# WP_STM32.net
KiCad netlist of a schematic drawn in Altium Designer
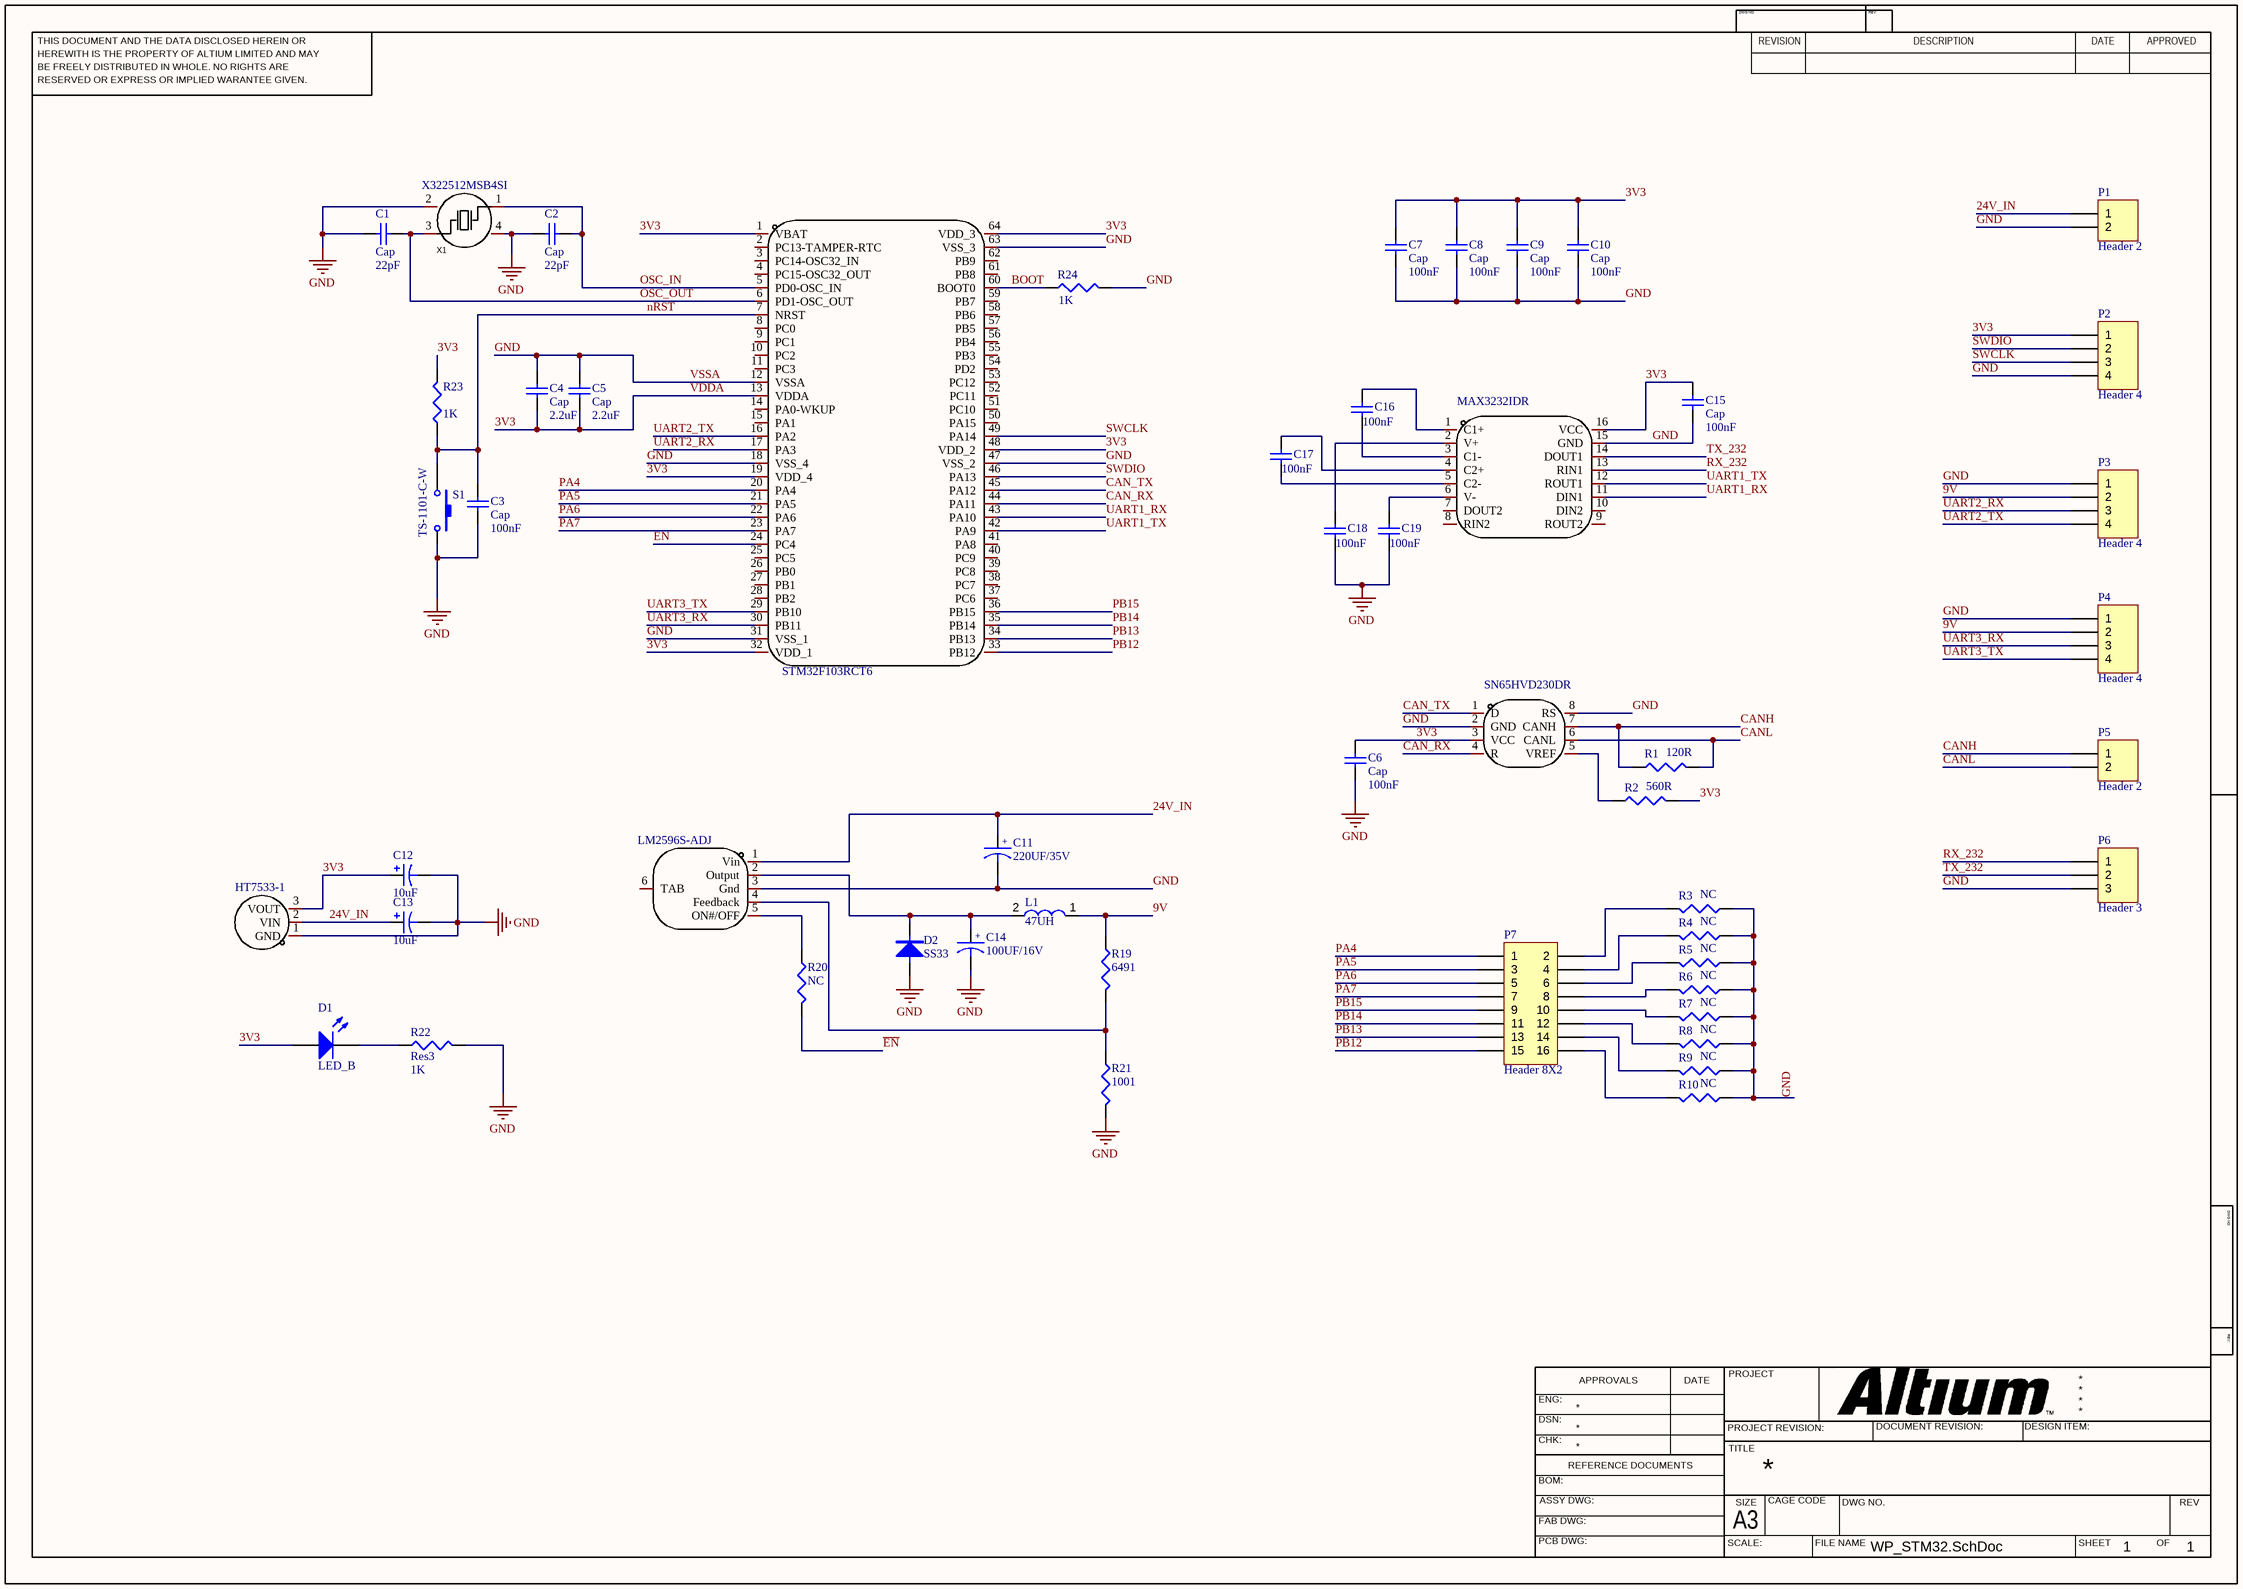
[diagram p0: WP_STM32.SchDoc]

(export (version "E")
  (design (tool "Eeschema 10.0.6"))
  (components
    (comp (ref "C1")
      (value "Cap")
      (footprint "0603C")
      (description "Capacitor")
      (fields (field (name "ALTIUM_VALUE") "22pF") (field (name "PUBLISHER") "Altium Limited"))
      (libsource (lib "Miscellaneous Devices") (part "Cap"))
    )
    (comp (ref "C2")
      (value "Cap")
      (footprint "0603C")
      (description "Capacitor")
      (fields (field (name "ALTIUM_VALUE") "22pF") (field (name "PUBLISHER") "Altium Limited"))
      (libsource (lib "Miscellaneous Devices") (part "Cap"))
    )
    (comp (ref "C3")
      (value "Cap")
      (footprint "0603C")
      (description "Capacitor")
      (fields (field (name "ALTIUM_VALUE") "100nF") (field (name "PUBLISHER") "Altium Limited"))
      (libsource (lib "Miscellaneous Devices") (part "Cap"))
    )
    (comp (ref "C4")
      (value "Cap")
      (footprint "0603C")
      (description "Capacitor")
      (fields (field (name "ALTIUM_VALUE") "2.2uF") (field (name "PUBLISHER") "Altium Limited"))
      (libsource (lib "Miscellaneous Devices") (part "Cap"))
    )
    (comp (ref "C5")
      (value "Cap")
      (footprint "0603C")
      (description "Capacitor")
      (fields (field (name "ALTIUM_VALUE") "2.2uF") (field (name "PUBLISHER") "Altium Limited"))
      (libsource (lib "Miscellaneous Devices") (part "Cap"))
    )
    (comp (ref "C6")
      (value "Cap")
      (footprint "0603C")
      (description "Capacitor")
      (fields (field (name "ALTIUM_VALUE") "100nF") (field (name "PUBLISHER") "Altium Limited"))
      (libsource (lib "Miscellaneous Devices") (part "Cap"))
    )
    (comp (ref "C7")
      (value "Cap")
      (footprint "0603C")
      (description "Capacitor")
      (fields (field (name "ALTIUM_VALUE") "100nF") (field (name "PUBLISHER") "Altium Limited"))
      (libsource (lib "Miscellaneous Devices") (part "Cap"))
    )
    (comp (ref "C8")
      (value "Cap")
      (footprint "0603C")
      (description "Capacitor")
      (fields (field (name "ALTIUM_VALUE") "100nF") (field (name "PUBLISHER") "Altium Limited"))
      (libsource (lib "Miscellaneous Devices") (part "Cap"))
    )
    (comp (ref "C9")
      (value "Cap")
      (footprint "0603C")
      (description "Capacitor")
      (fields (field (name "ALTIUM_VALUE") "100nF") (field (name "PUBLISHER") "Altium Limited"))
      (libsource (lib "Miscellaneous Devices") (part "Cap"))
    )
    (comp (ref "C10")
      (value "Cap")
      (footprint "0603C")
      (description "Capacitor")
      (fields (field (name "ALTIUM_VALUE") "100nF") (field (name "PUBLISHER") "Altium Limited"))
      (libsource (lib "Miscellaneous Devices") (part "Cap"))
    )
    (comp (ref "C11")
      (value "220UF/35V")
      (footprint "CAP-TH_BD8.0-P3.50-D0.6-FD")
      (libsource (lib "*") (part "C+"))
    )
    (comp (ref "C12")
      (value "10uF")
      (footprint "LC-CASE-A_3216")
      (description "Polarized Capacitor (Surface Mount)")
      (fields (field (name "Comment") "Cap Pol3") (field (name "PUBLISHER") "Altium Limited"))
      (libsource (lib "Miscellaneous Devices") (part "Cap Pol3"))
    )
    (comp (ref "C13")
      (value "10uF")
      (footprint "LC-CASE-A_3216")
      (description "Polarized Capacitor (Surface Mount)")
      (fields (field (name "Comment") "Cap Pol3") (field (name "PUBLISHER") "Altium Limited"))
      (libsource (lib "Miscellaneous Devices") (part "Cap Pol3"))
    )
    (comp (ref "C14")
      (value "100UF/16V")
      (footprint "CAP-TH_BD5.0-P2.00-D0.5-FD-1")
      (libsource (lib "*") (part "C+"))
    )
    (comp (ref "C15")
      (value "Cap")
      (footprint "0603C")
      (description "Capacitor")
      (fields (field (name "ALTIUM_VALUE") "100nF") (field (name "PUBLISHER") "Altium Limited"))
      (libsource (lib "Miscellaneous Devices") (part "Cap"))
    )
    (comp (ref "C16")
      (value "100nF")
      (footprint "0603C")
      (description "Capacitor")
      (fields (field (name "Comment") "Cap") (field (name "PUBLISHER") "Altium Limited"))
      (libsource (lib "Miscellaneous Devices") (part "Cap"))
    )
    (comp (ref "C17")
      (value "100nF")
      (footprint "0603C")
      (description "Capacitor")
      (fields (field (name "Comment") "Cap") (field (name "PUBLISHER") "Altium Limited"))
      (libsource (lib "Miscellaneous Devices") (part "Cap"))
    )
    (comp (ref "C18")
      (value "100nF")
      (footprint "0603C")
      (description "Capacitor")
      (fields (field (name "Comment") "Cap") (field (name "PUBLISHER") "Altium Limited"))
      (libsource (lib "Miscellaneous Devices") (part "Cap"))
    )
    (comp (ref "C19")
      (value "100nF")
      (footprint "0603C")
      (description "Capacitor")
      (fields (field (name "Comment") "Cap") (field (name "PUBLISHER") "Altium Limited"))
      (libsource (lib "Miscellaneous Devices") (part "Cap"))
    )
    (comp (ref "D1")
      (value "LED_B")
      (footprint "0603D")
      (description "Typical RED, GREEN, YELLOW, AMBER GaAs LED")
      (fields (field (name "PUBLISHER") "Altium Limited"))
      (libsource (lib "Miscellaneous Devices") (part "LED2"))
    )
    (comp (ref "D2") (value "SS33") (footprint "LC-SMA(DO-214AC)") (libsource (lib "*") (part "D")))
    (comp (ref "L1")
      (value "47UH")
      (footprint "IND-SMD_L10.8-W10.0_SLO1040H")
      (libsource (lib "*") (part "L"))
    )
    (comp (ref "P1")
      (value "Header 2")
      (footprint "KF350-2P")
      (description "Header, 2-Pin")
      (fields (field (name "PUBLISHER") "Altium Limited"))
      (libsource (lib "Miscellaneous Connectors") (part "Header 2"))
    )
    (comp (ref "P2")
      (value "Header 4")
      (footprint "MX 1.25-LI-4P")
      (description "Header, 4-Pin")
      (fields (field (name "PUBLISHER") "Altium Limited"))
      (libsource (lib "Miscellaneous Connectors") (part "Header 4"))
    )
    (comp (ref "P3")
      (value "Header 4")
      (footprint "MX 1.25-LI-4P")
      (description "Header, 4-Pin")
      (fields (field (name "PUBLISHER") "Altium Limited"))
      (libsource (lib "Miscellaneous Connectors") (part "Header 4"))
    )
    (comp (ref "P4")
      (value "Header 4")
      (footprint "MX 1.25-LI-4P")
      (description "Header, 4-Pin")
      (fields (field (name "PUBLISHER") "Altium Limited"))
      (libsource (lib "Miscellaneous Connectors") (part "Header 4"))
    )
    (comp (ref "P5")
      (value "Header 2")
      (footprint "MX 1.25-LI-2P")
      (description "Header, 2-Pin")
      (fields (field (name "PUBLISHER") "Altium Limited"))
      (libsource (lib "Miscellaneous Connectors") (part "Header 2"))
    )
    (comp (ref "P6")
      (value "Header 3")
      (footprint "MX 1.25-LI-3P")
      (description "Header, 3-Pin")
      (fields (field (name "PUBLISHER") "Altium Limited"))
      (libsource (lib "Miscellaneous Connectors") (part "Header 3"))
    )
    (comp (ref "P7")
      (value "Header 8X2")
      (footprint "HDR2X8")
      (description "Header, 8-Pin, Dual row")
      (fields (field (name "PUBLISHER") "Altium Limited"))
      (libsource (lib "Miscellaneous Connectors") (part "Header 8X2"))
    )
    (comp (ref "R1")
      (value "120R")
      (footprint "0603R")
      (description "Resistor")
      (fields (field (name "Comment") "Res3") (field (name "PUBLISHER") "Altium Limited"))
      (libsource (lib "Miscellaneous Devices") (part "Res3"))
    )
    (comp (ref "R2")
      (value "560R")
      (footprint "0603R")
      (description "Resistor")
      (fields (field (name "Comment") "Res3") (field (name "PUBLISHER") "Altium Limited"))
      (libsource (lib "Miscellaneous Devices") (part "Res3"))
    )
    (comp (ref "R3")
      (value "NC")
      (footprint "0603R")
      (description "Resistor")
      (fields (field (name "Comment") "Res3") (field (name "PUBLISHER") "Altium Limited"))
      (libsource (lib "Miscellaneous Devices") (part "Res3"))
    )
    (comp (ref "R4")
      (value "NC")
      (footprint "0603R")
      (description "Resistor")
      (fields (field (name "Comment") "Res3") (field (name "PUBLISHER") "Altium Limited"))
      (libsource (lib "Miscellaneous Devices") (part "Res3"))
    )
    (comp (ref "R5")
      (value "NC")
      (footprint "0603R")
      (description "Resistor")
      (fields (field (name "Comment") "Res3") (field (name "PUBLISHER") "Altium Limited"))
      (libsource (lib "Miscellaneous Devices") (part "Res3"))
    )
    (comp (ref "R6")
      (value "NC")
      (footprint "0603R")
      (description "Resistor")
      (fields (field (name "Comment") "Res3") (field (name "PUBLISHER") "Altium Limited"))
      (libsource (lib "Miscellaneous Devices") (part "Res3"))
    )
    (comp (ref "R7")
      (value "NC")
      (footprint "0603R")
      (description "Resistor")
      (fields (field (name "Comment") "Res3") (field (name "PUBLISHER") "Altium Limited"))
      (libsource (lib "Miscellaneous Devices") (part "Res3"))
    )
    (comp (ref "R8")
      (value "NC")
      (footprint "0603R")
      (description "Resistor")
      (fields (field (name "Comment") "Res3") (field (name "PUBLISHER") "Altium Limited"))
      (libsource (lib "Miscellaneous Devices") (part "Res3"))
    )
    (comp (ref "R9")
      (value "NC")
      (footprint "0603R")
      (description "Resistor")
      (fields (field (name "Comment") "Res3") (field (name "PUBLISHER") "Altium Limited"))
      (libsource (lib "Miscellaneous Devices") (part "Res3"))
    )
    (comp (ref "R10")
      (value "NC")
      (footprint "0603R")
      (description "Resistor")
      (fields (field (name "Comment") "Res3") (field (name "PUBLISHER") "Altium Limited"))
      (libsource (lib "Miscellaneous Devices") (part "Res3"))
    )
    (comp (ref "R19")
      (value "6491")
      (footprint "0603R")
      (description "Resistor")
      (fields (field (name "Comment") "Res3") (field (name "PUBLISHER") "Altium Limited"))
      (libsource (lib "Miscellaneous Devices") (part "Res3"))
    )
    (comp (ref "R20")
      (value "NC")
      (footprint "0603R")
      (description "Resistor")
      (fields (field (name "Comment") "Res3") (field (name "PUBLISHER") "Altium Limited"))
      (libsource (lib "Miscellaneous Devices") (part "Res3"))
    )
    (comp (ref "R21")
      (value "1001")
      (footprint "0603R")
      (description "Resistor")
      (fields (field (name "Comment") "Res3") (field (name "PUBLISHER") "Altium Limited"))
      (libsource (lib "Miscellaneous Devices") (part "Res3"))
    )
    (comp (ref "R22")
      (value "Res3")
      (footprint "0603R")
      (description "Resistor")
      (fields (field (name "ALTIUM_VALUE") "1K") (field (name "PUBLISHER") "Altium Limited"))
      (libsource (lib "Miscellaneous Devices") (part "Res3"))
    )
    (comp (ref "R23")
      (value "1K")
      (footprint "0603R")
      (description "Resistor")
      (fields (field (name "Comment") "Res3") (field (name "PUBLISHER") "Altium Limited"))
      (libsource (lib "Miscellaneous Devices") (part "Res3"))
    )
    (comp (ref "R24")
      (value "1K")
      (footprint "0603R")
      (description "Resistor")
      (fields (field (name "Comment") "Res3") (field (name "PUBLISHER") "Altium Limited"))
      (libsource (lib "Miscellaneous Devices") (part "Res3"))
    )
    (comp (ref "S1")
      (value "TS-1101-C-W")
      (footprint "SW-SMD_L3.9-W3.0-P4.45")
      (description "Switch")
      (fields (field (name "PUBLISHER") "Altium Limited"))
      (libsource (lib "Miscellaneous Devices") (part "SW-PB"))
    )
    (comp (ref "U1")
      (value "STM32F103RCT6")
      (footprint "LQFP-64_L10.0-W10.0-P0.50-LS12.0-BL")
      (fields (field (name "MANUFACTURER") "ST(意法半导体)"))
      (libsource (lib "altium-import") (part "root_0_STM32F103RCT6_"))
    )
    (comp (ref "U2")
      (value "SN65HVD230DR")
      (footprint "SOP8")
      (fields (field (name "MANUFACTURER") "TI(德州仪器)"))
      (libsource (lib "altium-import") (part "root_0_SN65HVD230DR_"))
    )
    (comp (ref "U3")
      (value "LM2596S-ADJ")
      (footprint "TO-263-5_L10.2-W8.9-P1.70-BR")
      (fields (field (name "MANUFACTURER") "UMW(友台半导体)"))
      (libsource (lib "altium-import") (part "root_0_mirrored_LM2596S-ADJ_C347423_"))
    )
    (comp (ref "U4")
      (value "HT7533-1")
      (footprint "SOT89")
      (fields (field (name "MANUFACTURER") "UMW(友台半导体)"))
      (libsource (lib "altium-import") (part "root_2_HT7533-1_C347186_"))
    )
    (comp (ref "U5")
      (value "MAX3232IDR")
      (footprint "SOP16")
      (fields (field (name "MANUFACTURER") "TI(德州仪器)"))
      (libsource (lib "altium-import") (part "root_0_MAX3232IDR_"))
    )
    (comp (ref "X1")
      (value "X322512MSB4SI")
      (footprint "OSC-SMD_4P-L3.2-W2.5-BL")
      (fields (field (name "MANUFACTURER") "YXC(扬兴晶振)"))
      (libsource (lib "altium-import") (part "root_2_X322512MSB4SI_"))
    )
  )
  (nets
    (net (code "1") (name "/3V3") (class "Default")
      (node (ref "C10") (pin "2") (pinfunction "2_2") (pintype "passive"))
      (node (ref "C12") (pin "1") (pinfunction "1_1") (pintype "passive"))
      (node (ref "C15") (pin "1") (pinfunction "1_1") (pintype "passive"))
      (node (ref "C4") (pin "1") (pinfunction "1_1") (pintype "passive"))
      (node (ref "C5") (pin "1") (pinfunction "1_1") (pintype "passive"))
      (node (ref "C6") (pin "2") (pinfunction "2_2") (pintype "passive"))
      (node (ref "C7") (pin "2") (pinfunction "2_2") (pintype "passive"))
      (node (ref "C8") (pin "2") (pinfunction "2_2") (pintype "passive"))
      (node (ref "C9") (pin "2") (pinfunction "2_2") (pintype "passive"))
      (node (ref "D1") (pin "1") (pinfunction "A_1") (pintype "passive"))
      (node (ref "P2") (pin "1") (pinfunction "1_1") (pintype "passive"))
      (node (ref "R2") (pin "2") (pinfunction "2_2") (pintype "passive"))
      (node (ref "R23") (pin "2") (pinfunction "2_2") (pintype "passive"))
      (node (ref "U1") (pin "1") (pinfunction "VBAT_1") (pintype "passive"))
      (node (ref "U1") (pin "13") (pinfunction "VDDA_13") (pintype "passive"))
      (node (ref "U1") (pin "19") (pinfunction "VDD_4_19") (pintype "passive"))
      (node (ref "U1") (pin "32") (pinfunction "VDD_1_32") (pintype "passive"))
      (node (ref "U1") (pin "48") (pinfunction "VDD_2_48") (pintype "passive"))
      (node (ref "U1") (pin "64") (pinfunction "VDD_3_64") (pintype "passive"))
      (node (ref "U2") (pin "3") (pinfunction "VCC_3") (pintype "passive"))
      (node (ref "U4") (pin "3") (pinfunction "VOUT_3") (pintype "passive"))
      (node (ref "U5") (pin "16") (pinfunction "VCC_16") (pintype "passive"))
    )
    (net (code "2") (name "/9V") (class "Default")
      (node (ref "L1") (pin "1") (pinfunction "1_1") (pintype "passive"))
      (node (ref "P3") (pin "2") (pinfunction "2_2") (pintype "passive"))
      (node (ref "P4") (pin "2") (pinfunction "2_2") (pintype "passive"))
      (node (ref "R19") (pin "1") (pinfunction "1_1") (pintype "passive"))
    )
    (net (code "3") (name "/24V_IN") (class "Default")
      (node (ref "C11") (pin "1") (pinfunction "1_1") (pintype "passive"))
      (node (ref "C13") (pin "1") (pinfunction "1_1") (pintype "passive"))
      (node (ref "P1") (pin "1") (pinfunction "1_1") (pintype "passive"))
      (node (ref "U3") (pin "1") (pinfunction "Vin_1") (pintype "passive"))
      (node (ref "U4") (pin "2") (pinfunction "VIN_2") (pintype "passive"))
    )
    (net (code "5") (name "/BOOT") (class "Default")
      (node (ref "R24") (pin "1") (pinfunction "1_1") (pintype "passive"))
      (node (ref "U1") (pin "60") (pinfunction "BOOT0_60") (pintype "passive"))
    )
    (net (code "6") (name "/CANH") (class "Default")
      (node (ref "P5") (pin "1") (pinfunction "1_1") (pintype "passive"))
      (node (ref "R1") (pin "1") (pinfunction "1_1") (pintype "passive"))
      (node (ref "U2") (pin "7") (pinfunction "CANH_7") (pintype "passive"))
    )
    (net (code "7") (name "/CANL") (class "Default")
      (node (ref "P5") (pin "2") (pinfunction "2_2") (pintype "passive"))
      (node (ref "R1") (pin "2") (pinfunction "2_2") (pintype "passive"))
      (node (ref "U2") (pin "6") (pinfunction "CANL_6") (pintype "passive"))
    )
    (net (code "8") (name "/CAN_RX") (class "Default")
      (node (ref "U1") (pin "44") (pinfunction "PA11_44") (pintype "passive"))
      (node (ref "U2") (pin "4") (pinfunction "R_4") (pintype "passive"))
    )
    (net (code "9") (name "/CAN_TX") (class "Default")
      (node (ref "U1") (pin "45") (pinfunction "PA12_45") (pintype "passive"))
      (node (ref "U2") (pin "1") (pinfunction "D_1") (pintype "passive"))
    )
    (net (code "10") (name "/OSC_IN") (class "Default")
      (node (ref "C2") (pin "2") (pinfunction "2_2") (pintype "passive"))
      (node (ref "U1") (pin "5") (pinfunction "PD0-OSC_IN_5") (pintype "passive"))
      (node (ref "X1") (pin "1") (pinfunction "OSC1_1") (pintype "passive"))
    )
    (net (code "11") (name "/OSC_OUT") (class "Default")
      (node (ref "C1") (pin "2") (pinfunction "2_2") (pintype "passive"))
      (node (ref "U1") (pin "6") (pinfunction "PD1-OSC_OUT_6") (pintype "passive"))
      (node (ref "X1") (pin "3") (pinfunction "OSC2_3") (pintype "passive"))
    )
    (net (code "12") (name "/PA4") (class "Default")
      (node (ref "P7") (pin "1") (pinfunction "1_1") (pintype "passive"))
      (node (ref "U1") (pin "20") (pinfunction "PA4_20") (pintype "passive"))
    )
    (net (code "13") (name "/PA5") (class "Default")
      (node (ref "P7") (pin "3") (pinfunction "3_3") (pintype "passive"))
      (node (ref "U1") (pin "21") (pinfunction "PA5_21") (pintype "passive"))
    )
    (net (code "14") (name "/PA6") (class "Default")
      (node (ref "P7") (pin "5") (pinfunction "5_5") (pintype "passive"))
      (node (ref "U1") (pin "22") (pinfunction "PA6_22") (pintype "passive"))
    )
    (net (code "15") (name "/PA7") (class "Default")
      (node (ref "P7") (pin "7") (pinfunction "7_7") (pintype "passive"))
      (node (ref "U1") (pin "23") (pinfunction "PA7_23") (pintype "passive"))
    )
    (net (code "16") (name "/PB12") (class "Default")
      (node (ref "P7") (pin "15") (pinfunction "15_15") (pintype "passive"))
      (node (ref "U1") (pin "33") (pinfunction "PB12_33") (pintype "passive"))
    )
    (net (code "17") (name "/PB13") (class "Default")
      (node (ref "P7") (pin "13") (pinfunction "13_13") (pintype "passive"))
      (node (ref "U1") (pin "34") (pinfunction "PB13_34") (pintype "passive"))
    )
    (net (code "18") (name "/PB14") (class "Default")
      (node (ref "P7") (pin "11") (pinfunction "11_11") (pintype "passive"))
      (node (ref "U1") (pin "35") (pinfunction "PB14_35") (pintype "passive"))
    )
    (net (code "19") (name "/PB15") (class "Default")
      (node (ref "P7") (pin "9") (pinfunction "9_9") (pintype "passive"))
      (node (ref "U1") (pin "36") (pinfunction "PB15_36") (pintype "passive"))
    )
    (net (code "20") (name "/RX_232") (class "Default")
      (node (ref "P6") (pin "1") (pinfunction "1_1") (pintype "passive"))
      (node (ref "U5") (pin "13") (pinfunction "RIN1_13") (pintype "passive"))
    )
    (net (code "21") (name "/SWCLK") (class "Default")
      (node (ref "P2") (pin "3") (pinfunction "3_3") (pintype "passive"))
      (node (ref "U1") (pin "49") (pinfunction "PA14_49") (pintype "passive"))
    )
    (net (code "22") (name "/SWDIO") (class "Default")
      (node (ref "P2") (pin "2") (pinfunction "2_2") (pintype "passive"))
      (node (ref "U1") (pin "46") (pinfunction "PA13_46") (pintype "passive"))
    )
    (net (code "23") (name "/TX_232") (class "Default")
      (node (ref "P6") (pin "2") (pinfunction "2_2") (pintype "passive"))
      (node (ref "U5") (pin "14") (pinfunction "DOUT1_14") (pintype "passive"))
    )
    (net (code "24") (name "/UART1_RX") (class "Default")
      (node (ref "U1") (pin "43") (pinfunction "PA10_43") (pintype "passive"))
      (node (ref "U5") (pin "11") (pinfunction "DIN1_11") (pintype "passive"))
    )
    (net (code "25") (name "/UART1_TX") (class "Default")
      (node (ref "U1") (pin "42") (pinfunction "PA9_42") (pintype "passive"))
      (node (ref "U5") (pin "12") (pinfunction "ROUT1_12") (pintype "passive"))
    )
    (net (code "26") (name "/UART2_RX") (class "Default")
      (node (ref "P3") (pin "3") (pinfunction "3_3") (pintype "passive"))
      (node (ref "U1") (pin "17") (pinfunction "PA3_17") (pintype "passive"))
    )
    (net (code "27") (name "/UART2_TX") (class "Default")
      (node (ref "P3") (pin "4") (pinfunction "4_4") (pintype "passive"))
      (node (ref "U1") (pin "16") (pinfunction "PA2_16") (pintype "passive"))
    )
    (net (code "28") (name "/UART3_RX") (class "Default")
      (node (ref "P4") (pin "3") (pinfunction "3_3") (pintype "passive"))
      (node (ref "U1") (pin "30") (pinfunction "PB11_30") (pintype "passive"))
    )
    (net (code "29") (name "/UART3_TX") (class "Default")
      (node (ref "P4") (pin "4") (pinfunction "4_4") (pintype "passive"))
      (node (ref "U1") (pin "29") (pinfunction "PB10_29") (pintype "passive"))
    )
    (net (code "30") (name "/nRST") (class "Default")
      (node (ref "C3") (pin "1") (pinfunction "1_1") (pintype "passive"))
      (node (ref "R23") (pin "1") (pinfunction "1_1") (pintype "passive"))
      (node (ref "S1") (pin "1") (pinfunction "1_1") (pintype "passive"))
      (node (ref "U1") (pin "7") (pinfunction "NRST_7") (pintype "passive"))
    )
    (net (code "31") (name "/~{EN}") (class "Default")
      (node (ref "R20") (pin "2") (pinfunction "2_2") (pintype "passive"))
      (node (ref "U1") (pin "24") (pinfunction "PC4_24") (pintype "passive"))
    )
    (net (code "32") (name "GND") (class "Default")
      (node (ref "C1") (pin "1") (pinfunction "1_1") (pintype "passive"))
      (node (ref "C10") (pin "1") (pinfunction "1_1") (pintype "passive"))
      (node (ref "C11") (pin "2") (pinfunction "2_2") (pintype "passive"))
      (node (ref "C12") (pin "2") (pinfunction "2_2") (pintype "passive"))
      (node (ref "C13") (pin "2") (pinfunction "2_2") (pintype "passive"))
      (node (ref "C14") (pin "2") (pinfunction "2_2") (pintype "passive"))
      (node (ref "C15") (pin "2") (pinfunction "2_2") (pintype "passive"))
      (node (ref "C18") (pin "2") (pinfunction "2_2") (pintype "passive"))
      (node (ref "C19") (pin "2") (pinfunction "2_2") (pintype "passive"))
      (node (ref "C2") (pin "1") (pinfunction "1_1") (pintype "passive"))
      (node (ref "C3") (pin "2") (pinfunction "2_2") (pintype "passive"))
      (node (ref "C4") (pin "2") (pinfunction "2_2") (pintype "passive"))
      (node (ref "C5") (pin "2") (pinfunction "2_2") (pintype "passive"))
      (node (ref "C6") (pin "1") (pinfunction "1_1") (pintype "passive"))
      (node (ref "C7") (pin "1") (pinfunction "1_1") (pintype "passive"))
      (node (ref "C8") (pin "1") (pinfunction "1_1") (pintype "passive"))
      (node (ref "C9") (pin "1") (pinfunction "1_1") (pintype "passive"))
      (node (ref "D2") (pin "1") (pinfunction "A_1") (pintype "passive"))
      (node (ref "P1") (pin "2") (pinfunction "2_2") (pintype "passive"))
      (node (ref "P2") (pin "4") (pinfunction "4_4") (pintype "passive"))
      (node (ref "P3") (pin "1") (pinfunction "1_1") (pintype "passive"))
      (node (ref "P4") (pin "1") (pinfunction "1_1") (pintype "passive"))
      (node (ref "P6") (pin "3") (pinfunction "3_3") (pintype "passive"))
      (node (ref "R10") (pin "1") (pinfunction "1_1") (pintype "passive"))
      (node (ref "R21") (pin "2") (pinfunction "2_2") (pintype "passive"))
      (node (ref "R22") (pin "2") (pinfunction "2_2") (pintype "passive"))
      (node (ref "R24") (pin "2") (pinfunction "2_2") (pintype "passive"))
      (node (ref "R3") (pin "1") (pinfunction "1_1") (pintype "passive"))
      (node (ref "R4") (pin "1") (pinfunction "1_1") (pintype "passive"))
      (node (ref "R5") (pin "1") (pinfunction "1_1") (pintype "passive"))
      (node (ref "R6") (pin "1") (pinfunction "1_1") (pintype "passive"))
      (node (ref "R7") (pin "1") (pinfunction "1_1") (pintype "passive"))
      (node (ref "R8") (pin "1") (pinfunction "1_1") (pintype "passive"))
      (node (ref "R9") (pin "1") (pinfunction "1_1") (pintype "passive"))
      (node (ref "S1") (pin "2") (pinfunction "2_2") (pintype "passive"))
      (node (ref "U1") (pin "12") (pinfunction "VSSA_12") (pintype "passive"))
      (node (ref "U1") (pin "18") (pinfunction "VSS_4_18") (pintype "passive"))
      (node (ref "U1") (pin "31") (pinfunction "VSS_1_31") (pintype "passive"))
      (node (ref "U1") (pin "47") (pinfunction "VSS_2_47") (pintype "passive"))
      (node (ref "U1") (pin "63") (pinfunction "VSS_3_63") (pintype "passive"))
      (node (ref "U2") (pin "2") (pinfunction "GND_2") (pintype "passive"))
      (node (ref "U2") (pin "8") (pinfunction "RS_8") (pintype "passive"))
      (node (ref "U3") (pin "3") (pinfunction "Gnd_3") (pintype "passive"))
      (node (ref "U4") (pin "1") (pinfunction "GND_1") (pintype "passive"))
      (node (ref "U5") (pin "15") (pinfunction "GND_15") (pintype "passive"))
      (node (ref "X1") (pin "2") (pinfunction "GND_2") (pintype "passive"))
      (node (ref "X1") (pin "4") (pinfunction "GND_4") (pintype "passive"))
    )
    (net (code "33") (name "Net-(D1-K)") (class "Default")
      (node (ref "D1") (pin "2") (pinfunction "K_2") (pintype "passive"))
      (node (ref "R22") (pin "1") (pinfunction "1_1") (pintype "passive"))
    )
    (net (code "34") (name "Net-(D2-K)") (class "Default")
      (node (ref "C14") (pin "1") (pinfunction "1_1") (pintype "passive"))
      (node (ref "D2") (pin "2") (pinfunction "K_2") (pintype "passive"))
      (node (ref "L1") (pin "2") (pinfunction "2_2") (pintype "passive"))
      (node (ref "U3") (pin "2") (pinfunction "Output_2") (pintype "passive"))
    )
    (net (code "35") (name "Net-(P7-Pad2)") (class "Default")
      (node (ref "P7") (pin "2") (pinfunction "2_2") (pintype "passive"))
      (node (ref "R3") (pin "2") (pinfunction "2_2") (pintype "passive"))
    )
    (net (code "36") (name "Net-(P7-Pad4)") (class "Default")
      (node (ref "P7") (pin "4") (pinfunction "4_4") (pintype "passive"))
      (node (ref "R4") (pin "2") (pinfunction "2_2") (pintype "passive"))
    )
    (net (code "37") (name "Net-(P7-Pad6)") (class "Default")
      (node (ref "P7") (pin "6") (pinfunction "6_6") (pintype "passive"))
      (node (ref "R5") (pin "2") (pinfunction "2_2") (pintype "passive"))
    )
    (net (code "38") (name "Net-(P7-Pad8)") (class "Default")
      (node (ref "P7") (pin "8") (pinfunction "8_8") (pintype "passive"))
      (node (ref "R6") (pin "2") (pinfunction "2_2") (pintype "passive"))
    )
    (net (code "39") (name "Net-(P7-Pad10)") (class "Default")
      (node (ref "P7") (pin "10") (pinfunction "10_10") (pintype "passive"))
      (node (ref "R7") (pin "2") (pinfunction "2_2") (pintype "passive"))
    )
    (net (code "40") (name "Net-(P7-Pad12)") (class "Default")
      (node (ref "P7") (pin "12") (pinfunction "12_12") (pintype "passive"))
      (node (ref "R8") (pin "2") (pinfunction "2_2") (pintype "passive"))
    )
    (net (code "41") (name "Net-(P7-Pad14)") (class "Default")
      (node (ref "P7") (pin "14") (pinfunction "14_14") (pintype "passive"))
      (node (ref "R9") (pin "2") (pinfunction "2_2") (pintype "passive"))
    )
    (net (code "42") (name "Net-(P7-Pad16)") (class "Default")
      (node (ref "P7") (pin "16") (pinfunction "16_16") (pintype "passive"))
      (node (ref "R10") (pin "2") (pinfunction "2_2") (pintype "passive"))
    )
    (net (code "43") (name "Net-(U2-VREF)") (class "Default")
      (node (ref "R2") (pin "1") (pinfunction "1_1") (pintype "passive"))
      (node (ref "U2") (pin "5") (pinfunction "VREF_5") (pintype "passive"))
    )
    (net (code "44") (name "Net-(U3-Feedback)") (class "Default")
      (node (ref "R19") (pin "2") (pinfunction "2_2") (pintype "passive"))
      (node (ref "R21") (pin "1") (pinfunction "1_1") (pintype "passive"))
      (node (ref "U3") (pin "4") (pinfunction "Feedback_4") (pintype "passive"))
    )
    (net (code "45") (name "Net-(U3-ON#{slash}OFF)") (class "Default")
      (node (ref "R20") (pin "1") (pinfunction "1_1") (pintype "passive"))
      (node (ref "U3") (pin "5") (pinfunction "ON#/OFF_5") (pintype "passive"))
    )
    (net (code "46") (name "Net-(U5-C1+)") (class "Default")
      (node (ref "C16") (pin "1") (pinfunction "1_1") (pintype "passive"))
      (node (ref "U5") (pin "1") (pinfunction "C1+_1") (pintype "passive"))
    )
    (net (code "47") (name "Net-(U5-C1-)") (class "Default")
      (node (ref "C16") (pin "2") (pinfunction "2_2") (pintype "passive"))
      (node (ref "U5") (pin "3") (pinfunction "C1-_3") (pintype "passive"))
    )
    (net (code "48") (name "Net-(U5-C2+)") (class "Default")
      (node (ref "C17") (pin "1") (pinfunction "1_1") (pintype "passive"))
      (node (ref "U5") (pin "4") (pinfunction "C2+_4") (pintype "passive"))
    )
    (net (code "49") (name "Net-(U5-C2-)") (class "Default")
      (node (ref "C17") (pin "2") (pinfunction "2_2") (pintype "passive"))
      (node (ref "U5") (pin "5") (pinfunction "C2-_5") (pintype "passive"))
    )
    (net (code "50") (name "Net-(U5-V+)") (class "Default")
      (node (ref "C18") (pin "1") (pinfunction "1_1") (pintype "passive"))
      (node (ref "U5") (pin "2") (pinfunction "V+_2") (pintype "passive"))
    )
    (net (code "51") (name "Net-(U5-V-)") (class "Default")
      (node (ref "C19") (pin "1") (pinfunction "1_1") (pintype "passive"))
      (node (ref "U5") (pin "6") (pinfunction "V-_6") (pintype "passive"))
    )
    (net (code "52") (name "unconnected-(U1-PA0-WKUP-Pad14)") (class "Default")
      (node (ref "U1") (pin "14") (pinfunction "PA0-WKUP_14") (pintype "passive"))
    )
    (net (code "53") (name "unconnected-(U1-PA1-Pad15)") (class "Default")
      (node (ref "U1") (pin "15") (pinfunction "PA1_15") (pintype "passive"))
    )
    (net (code "54") (name "unconnected-(U1-PA8-Pad41)") (class "Default")
      (node (ref "U1") (pin "41") (pinfunction "PA8_41") (pintype "passive"))
    )
    (net (code "55") (name "unconnected-(U1-PA15-Pad50)") (class "Default")
      (node (ref "U1") (pin "50") (pinfunction "PA15_50") (pintype "passive"))
    )
    (net (code "56") (name "unconnected-(U1-PB0-Pad26)") (class "Default")
      (node (ref "U1") (pin "26") (pinfunction "PB0_26") (pintype "passive"))
    )
    (net (code "57") (name "unconnected-(U1-PB1-Pad27)") (class "Default")
      (node (ref "U1") (pin "27") (pinfunction "PB1_27") (pintype "passive"))
    )
    (net (code "58") (name "unconnected-(U1-PB2-Pad28)") (class "Default")
      (node (ref "U1") (pin "28") (pinfunction "PB2_28") (pintype "passive"))
    )
    (net (code "59") (name "unconnected-(U1-PB3-Pad55)") (class "Default")
      (node (ref "U1") (pin "55") (pinfunction "PB3_55") (pintype "passive"))
    )
    (net (code "60") (name "unconnected-(U1-PB4-Pad56)") (class "Default")
      (node (ref "U1") (pin "56") (pinfunction "PB4_56") (pintype "passive"))
    )
    (net (code "61") (name "unconnected-(U1-PB5-Pad57)") (class "Default")
      (node (ref "U1") (pin "57") (pinfunction "PB5_57") (pintype "passive"))
    )
    (net (code "62") (name "unconnected-(U1-PB6-Pad58)") (class "Default")
      (node (ref "U1") (pin "58") (pinfunction "PB6_58") (pintype "passive"))
    )
    (net (code "63") (name "unconnected-(U1-PB7-Pad59)") (class "Default")
      (node (ref "U1") (pin "59") (pinfunction "PB7_59") (pintype "passive"))
    )
    (net (code "64") (name "unconnected-(U1-PB8-Pad61)") (class "Default")
      (node (ref "U1") (pin "61") (pinfunction "PB8_61") (pintype "passive"))
    )
    (net (code "65") (name "unconnected-(U1-PB9-Pad62)") (class "Default")
      (node (ref "U1") (pin "62") (pinfunction "PB9_62") (pintype "passive"))
    )
    (net (code "66") (name "unconnected-(U1-PC0-Pad8)") (class "Default")
      (node (ref "U1") (pin "8") (pinfunction "PC0_8") (pintype "passive"))
    )
    (net (code "67") (name "unconnected-(U1-PC1-Pad9)") (class "Default")
      (node (ref "U1") (pin "9") (pinfunction "PC1_9") (pintype "passive"))
    )
    (net (code "68") (name "unconnected-(U1-PC2-Pad10)") (class "Default")
      (node (ref "U1") (pin "10") (pinfunction "PC2_10") (pintype "passive"))
    )
    (net (code "69") (name "unconnected-(U1-PC3-Pad11)") (class "Default")
      (node (ref "U1") (pin "11") (pinfunction "PC3_11") (pintype "passive"))
    )
    (net (code "70") (name "unconnected-(U1-PC5-Pad25)") (class "Default")
      (node (ref "U1") (pin "25") (pinfunction "PC5_25") (pintype "passive"))
    )
    (net (code "71") (name "unconnected-(U1-PC6-Pad37)") (class "Default")
      (node (ref "U1") (pin "37") (pinfunction "PC6_37") (pintype "passive"))
    )
    (net (code "72") (name "unconnected-(U1-PC7-Pad38)") (class "Default")
      (node (ref "U1") (pin "38") (pinfunction "PC7_38") (pintype "passive"))
    )
    (net (code "73") (name "unconnected-(U1-PC8-Pad39)") (class "Default")
      (node (ref "U1") (pin "39") (pinfunction "PC8_39") (pintype "passive"))
    )
    (net (code "74") (name "unconnected-(U1-PC9-Pad40)") (class "Default")
      (node (ref "U1") (pin "40") (pinfunction "PC9_40") (pintype "passive"))
    )
    (net (code "75") (name "unconnected-(U1-PC10-Pad51)") (class "Default")
      (node (ref "U1") (pin "51") (pinfunction "PC10_51") (pintype "passive"))
    )
    (net (code "76") (name "unconnected-(U1-PC11-Pad52)") (class "Default")
      (node (ref "U1") (pin "52") (pinfunction "PC11_52") (pintype "passive"))
    )
    (net (code "77") (name "unconnected-(U1-PC12-Pad53)") (class "Default")
      (node (ref "U1") (pin "53") (pinfunction "PC12_53") (pintype "passive"))
    )
    (net (code "78") (name "unconnected-(U1-PC13-TAMPER-RTC-Pad2)") (class "Default")
      (node (ref "U1") (pin "2") (pinfunction "PC13-TAMPER-RTC_2") (pintype "passive"))
    )
    (net (code "79") (name "unconnected-(U1-PC14-OSC32_IN-Pad3)") (class "Default")
      (node (ref "U1") (pin "3") (pinfunction "PC14-OSC32_IN_3") (pintype "passive"))
    )
    (net (code "80") (name "unconnected-(U1-PC15-OSC32_OUT-Pad4)") (class "Default")
      (node (ref "U1") (pin "4") (pinfunction "PC15-OSC32_OUT_4") (pintype "passive"))
    )
    (net (code "81") (name "unconnected-(U1-PD2-Pad54)") (class "Default")
      (node (ref "U1") (pin "54") (pinfunction "PD2_54") (pintype "passive"))
    )
    (net (code "82") (name "unconnected-(U3-TAB-Pad6)") (class "Default")
      (node (ref "U3") (pin "6") (pinfunction "TAB_6") (pintype "passive"))
    )
    (net (code "83") (name "unconnected-(U5-DIN2-Pad10)") (class "Default")
      (node (ref "U5") (pin "10") (pinfunction "DIN2_10") (pintype "passive"))
    )
    (net (code "84") (name "unconnected-(U5-DOUT2-Pad7)") (class "Default")
      (node (ref "U5") (pin "7") (pinfunction "DOUT2_7") (pintype "passive"))
    )
    (net (code "85") (name "unconnected-(U5-RIN2-Pad8)") (class "Default")
      (node (ref "U5") (pin "8") (pinfunction "RIN2_8") (pintype "passive"))
    )
    (net (code "86") (name "unconnected-(U5-ROUT2-Pad9)") (class "Default")
      (node (ref "U5") (pin "9") (pinfunction "ROUT2_9") (pintype "passive"))
    )
  )
)
